# 8051_at89s52.net
KiCad netlist of a schematic drawn in Altium Designer
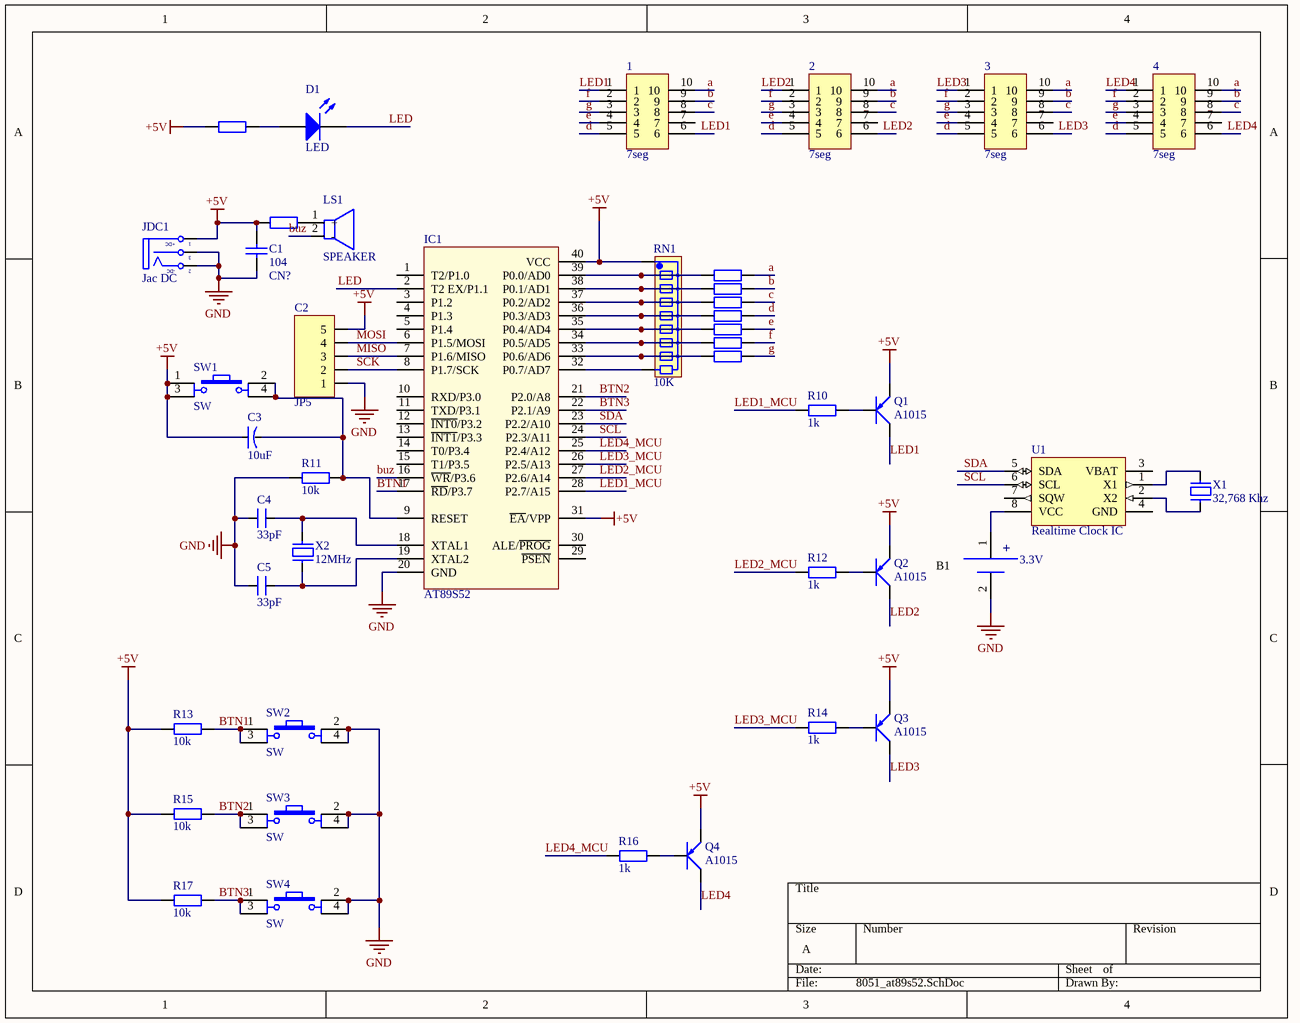
[diagram p0: 8051_at89s52.SchDoc]

(export (version "E")
  (design (tool "Eeschema 10.0.6"))
  (components
    (comp (ref "1")
      (value "7seg")
      (footprint "SM410361N")
      (description "7seg 0,36''")
      (libsource (lib "Schlib1") (part "SM410361N"))
    )
    (comp (ref "2")
      (value "7seg")
      (footprint "SM410361N")
      (description "7seg 0,36''")
      (libsource (lib "Schlib1") (part "SM410361N"))
    )
    (comp (ref "3")
      (value "7seg")
      (footprint "SM410361N")
      (description "7seg 0,36''")
      (libsource (lib "Schlib1") (part "SM410361N"))
    )
    (comp (ref "4")
      (value "7seg")
      (footprint "SM410361N")
      (description "7seg 0,36''")
      (libsource (lib "Schlib1") (part "SM410361N"))
    )
    (comp (ref "B1")
      (value "3.3V")
      (footprint "BATT-LI-Bott-22mm")
      (description "Battery holder")
      (fields
        (field (name "MANUFACTURER") "China")
        (field (name "Comment") "BATT-Holder")
        (field (name "PUBLISHER") "Hoang Nguyen")
      )
      (libsource (lib "hphonglib") (part "BATT-Holder"))
    )
    (comp (ref "C1")
      (value "104")
      (footprint "CAP_0805")
      (description "Capacitor (Semiconductor SIM Model)")
      (fields (field (name "ALTIUM_VALUE") "CN?") (field (name "PUBLISHER") "Altium Limited"))
      (libsource (lib "syhaunguyen") (part "Cap Semi"))
    )
    (comp (ref "C2")
      (value "JP5")
      (footprint "JP5-C1T")
      (description "WR-PHD 2.54 mm Angled Socket Header")
      (fields
        (field (name "MANUFACTURER") "Würth Elektronik eiSos GmbH")
        (field (name "PARTNO") "613005143121")
        (field (name "CREATED BY") "Karrer Zheng")
      )
      (libsource (lib "LIBRARY") (part "JP5"))
    )
    (comp (ref "C3")
      (value "10uF")
      (footprint "CA-ALU-2.54")
      (description "Capacitor (Semiconductor SIM Model)")
      (fields (field (name "PUBLISHER") "Altium Limited"))
      (libsource (lib "LIBRARY") (part "CN-ALU-DIP"))
    )
    (comp (ref "C4")
      (value "33pF")
      (footprint "CN1")
      (description "Cap np  1pF - 472pF")
      (libsource (lib "syhaunguyen") (part "CN1"))
    )
    (comp (ref "C5")
      (value "33pF")
      (footprint "CN1")
      (description "Cap np  1pF - 472pF")
      (libsource (lib "syhaunguyen") (part "CN1"))
    )
    (comp (ref "D1")
      (value "LED")
      (footprint "LED-0 5mm YELLOW")
      (description "Typical LED")
      (fields (field (name "PUBLISHER") "Altium Limited"))
      (libsource (lib "hphonglib") (part "LED"))
    )
    (comp (ref "IC1")
      (value "AT89S52")
      (footprint "DIP40/W0.6")
      (description "AT89S52, 8k Byte Flash Memory , 40 Pin")
      (libsource (lib "Schlib1") (part "AT89S52"))
    )
    (comp (ref "JDC1")
      (value "Jac DC")
      (footprint "DC3")
      (description "Jac DC input")
      (libsource (lib "LIBRARY") (part "DCIN"))
    )
    (comp (ref "LS1")
      (value "SPEAKER")
      (footprint "speaker")
      (fields (field (name "PUBLISHER") "Hoang Nguyen"))
      (libsource (lib "hphonglib") (part "SPEAKER"))
    )
    (comp (ref "Q1")
      (value "A1015")
      (footprint "QTO-92")
      (description "PNP 600mW, ECB")
      (libsource (lib "hphonglib") (part "A1015_1"))
    )
    (comp (ref "Q2")
      (value "A1015")
      (footprint "QTO-92")
      (description "PNP 600mW, ECB")
      (libsource (lib "hphonglib") (part "A1015_1"))
    )
    (comp (ref "Q3")
      (value "A1015")
      (footprint "QTO-92")
      (description "PNP 600mW, ECB")
      (libsource (lib "hphonglib") (part "A1015_1"))
    )
    (comp (ref "Q4")
      (value "A1015")
      (footprint "QTO-92")
      (description "PNP 600mW, ECB")
      (libsource (lib "hphonglib") (part "A1015_1"))
    )
    (comp (ref "R1")
      (value "1k")
      (footprint "R1/4W")
      (description "Resistor 1/4W")
      (libsource (lib "hphonglib") (part "R1/4W"))
    )
    (comp (ref "R2")
      (value "1k")
      (footprint "R1/4W")
      (description "Resistor 1/4W")
      (libsource (lib "hphonglib") (part "R1/4W"))
    )
    (comp (ref "R3")
      (value "1k")
      (footprint "R1/4W")
      (description "Resistor 1/4W")
      (libsource (lib "hphonglib") (part "R1/4W"))
    )
    (comp (ref "R4")
      (value "1k")
      (footprint "R1/4W")
      (description "Resistor 1/4W")
      (libsource (lib "hphonglib") (part "R1/4W"))
    )
    (comp (ref "R5")
      (value "1k")
      (footprint "R1/4W")
      (description "Resistor 1/4W")
      (libsource (lib "hphonglib") (part "R1/4W"))
    )
    (comp (ref "R6")
      (value "1k")
      (footprint "R1/4W")
      (description "Resistor 1/4W")
      (libsource (lib "hphonglib") (part "R1/4W"))
    )
    (comp (ref "R7")
      (value "1k")
      (footprint "R1/4W")
      (description "Resistor 1/4W")
      (libsource (lib "hphonglib") (part "R1/4W"))
    )
    (comp (ref "R8")
      (value "1k")
      (footprint "R1/4W")
      (description "Resistor 1/4W")
      (libsource (lib "hphonglib") (part "R1/4W"))
    )
    (comp (ref "R9")
      (value "1k")
      (footprint "R1/4W")
      (description "Resistor 1/4W")
      (libsource (lib "hphonglib") (part "R1/4W"))
    )
    (comp (ref "R10")
      (value "1k")
      (footprint "R1/4W")
      (description "Resistor 1/4W")
      (libsource (lib "hphonglib") (part "R1/4W"))
    )
    (comp (ref "R11")
      (value "10k")
      (footprint "RES-1/4W")
      (description "Resistor 1/4W")
      (libsource (lib "syhaunguyen") (part "R1/4W"))
    )
    (comp (ref "R12")
      (value "1k")
      (footprint "R1/4W")
      (description "Resistor 1/4W")
      (libsource (lib "hphonglib") (part "R1/4W"))
    )
    (comp (ref "R13")
      (value "10k")
      (footprint "R1/4W")
      (description "Resistor 1/4W")
      (libsource (lib "syhaunguyen") (part "R1/4W"))
    )
    (comp (ref "R14")
      (value "1k")
      (footprint "R1/4W")
      (description "Resistor 1/4W")
      (libsource (lib "hphonglib") (part "R1/4W"))
    )
    (comp (ref "R15")
      (value "10k")
      (footprint "R1/4W")
      (description "Resistor 1/4W")
      (libsource (lib "syhaunguyen") (part "R1/4W"))
    )
    (comp (ref "R16")
      (value "1k")
      (footprint "R1/4W")
      (description "Resistor 1/4W")
      (libsource (lib "hphonglib") (part "R1/4W"))
    )
    (comp (ref "R17")
      (value "10k")
      (footprint "R1/4W")
      (description "Resistor 1/4W")
      (libsource (lib "syhaunguyen") (part "R1/4W"))
    )
    (comp (ref "RN1")
      (value "10K")
      (footprint "RN8")
      (description "Resistor 8 (Thanh)")
      (libsource (lib "syhaunguyen") (part "RN8"))
    )
    (comp (ref "SW1")
      (value "SW")
      (footprint "SW4")
      (description "Switch button 4 pin")
      (libsource (lib "hphonglib") (part "SW4"))
    )
    (comp (ref "SW2")
      (value "SW")
      (footprint "SW4")
      (description "Switch button 4 pin")
      (libsource (lib "hphonglib") (part "SW4"))
    )
    (comp (ref "SW3")
      (value "SW")
      (footprint "SW4")
      (description "Switch button 4 pin")
      (libsource (lib "hphonglib") (part "SW4"))
    )
    (comp (ref "SW4")
      (value "SW")
      (footprint "SW4")
      (description "Switch button 4 pin")
      (libsource (lib "hphonglib") (part "SW4"))
    )
    (comp (ref "U1")
      (value "Realtime Clock IC")
      (footprint "DS1307.Dip8")
      (fields (field (name "MANUFACTURER") "Maxim"))
      (libsource (lib "hphonglib") (part "DS1307"))
    )
    (comp (ref "X1")
      (value "32,768 Khz")
      (footprint "XT32k")
      (description "Crystal 32,768kHz for timer real")
      (libsource (lib "hphonglib") (part "XT32k"))
    )
    (comp (ref "X2")
      (value "12MHz")
      (footprint "XT2")
      (description "Crystal For all Crystal 2pin.")
      (libsource (lib "syhaunguyen") (part "XT2"))
    )
  )
  (nets
    (net (code "1") (name "+5V") (class "Default")
      (node (ref "C1") (pin "2") (pinfunction "2_2") (pintype "passive"))
      (node (ref "C2") (pin "5") (pinfunction "5_5") (pintype "passive"))
      (node (ref "C3") (pin "1") (pinfunction "1_1") (pintype "passive"))
      (node (ref "IC1") (pin "31") (pinfunction "~{EA}/VPP_31") (pintype "passive"))
      (node (ref "IC1") (pin "40") (pinfunction "VCC_40") (pintype "passive"))
      (node (ref "JDC1") (pin "1") (pinfunction "T_1") (pintype "passive"))
      (node (ref "Q1") (pin "1") (pinfunction "E_1") (pintype "passive"))
      (node (ref "Q2") (pin "1") (pinfunction "E_1") (pintype "passive"))
      (node (ref "Q3") (pin "1") (pinfunction "E_1") (pintype "passive"))
      (node (ref "Q4") (pin "1") (pinfunction "E_1") (pintype "passive"))
      (node (ref "R1") (pin "1") (pinfunction "1_1") (pintype "passive"))
      (node (ref "R13") (pin "1") (pinfunction "1_1") (pintype "passive"))
      (node (ref "R15") (pin "1") (pinfunction "1_1") (pintype "passive"))
      (node (ref "R17") (pin "1") (pinfunction "1_1") (pintype "passive"))
      (node (ref "R2") (pin "1") (pinfunction "1_1") (pintype "passive"))
      (node (ref "RN1") (pin "1") (pinfunction "1_1") (pintype "passive"))
      (node (ref "SW1") (pin "1") (pintype "passive"))
      (node (ref "SW1") (pin "3") (pintype "passive"))
    )
    (net (code "2") (name "/BTN1") (class "Default")
      (node (ref "IC1") (pin "17") (pinfunction "~{RD}/P3.7_17") (pintype "passive"))
      (node (ref "R13") (pin "2") (pinfunction "2_2") (pintype "passive"))
      (node (ref "SW2") (pin "1") (pintype "passive"))
      (node (ref "SW2") (pin "3") (pintype "passive"))
    )
    (net (code "3") (name "/BTN2") (class "Default")
      (node (ref "IC1") (pin "21") (pinfunction "P2.0/A8_21") (pintype "passive"))
      (node (ref "R15") (pin "2") (pinfunction "2_2") (pintype "passive"))
      (node (ref "SW3") (pin "1") (pintype "passive"))
      (node (ref "SW3") (pin "3") (pintype "passive"))
    )
    (net (code "4") (name "/BTN3") (class "Default")
      (node (ref "IC1") (pin "22") (pinfunction "P2.1/A9_22") (pintype "passive"))
      (node (ref "R17") (pin "2") (pinfunction "2_2") (pintype "passive"))
      (node (ref "SW4") (pin "1") (pintype "passive"))
      (node (ref "SW4") (pin "3") (pintype "passive"))
    )
    (net (code "5") (name "/LED") (class "Default")
      (node (ref "D1") (pin "2") (pinfunction "K_2") (pintype "passive"))
      (node (ref "IC1") (pin "2") (pinfunction "T2_EX/P1.1_2") (pintype "passive"))
    )
    (net (code "6") (name "/LED1") (class "Default")
      (node (ref "1") (pin "1") (pinfunction "1_1") (pintype "passive"))
      (node (ref "1") (pin "6") (pinfunction "6_6") (pintype "passive"))
      (node (ref "Q1") (pin "2") (pinfunction "C_2") (pintype "passive"))
    )
    (net (code "7") (name "/LED1_MCU") (class "Default")
      (node (ref "IC1") (pin "28") (pinfunction "P2.7/A15_28") (pintype "passive"))
      (node (ref "R10") (pin "1") (pinfunction "1_1") (pintype "passive"))
    )
    (net (code "8") (name "/LED2") (class "Default")
      (node (ref "2") (pin "1") (pinfunction "1_1") (pintype "passive"))
      (node (ref "2") (pin "6") (pinfunction "6_6") (pintype "passive"))
      (node (ref "Q2") (pin "2") (pinfunction "C_2") (pintype "passive"))
    )
    (net (code "9") (name "/LED2_MCU") (class "Default")
      (node (ref "IC1") (pin "27") (pinfunction "P2.6/A14_27") (pintype "passive"))
      (node (ref "R12") (pin "1") (pinfunction "1_1") (pintype "passive"))
    )
    (net (code "10") (name "/LED3") (class "Default")
      (node (ref "3") (pin "1") (pinfunction "1_1") (pintype "passive"))
      (node (ref "3") (pin "6") (pinfunction "6_6") (pintype "passive"))
      (node (ref "Q3") (pin "2") (pinfunction "C_2") (pintype "passive"))
    )
    (net (code "11") (name "/LED3_MCU") (class "Default")
      (node (ref "IC1") (pin "26") (pinfunction "P2.5/A13_26") (pintype "passive"))
      (node (ref "R14") (pin "1") (pinfunction "1_1") (pintype "passive"))
    )
    (net (code "12") (name "/LED4") (class "Default")
      (node (ref "4") (pin "1") (pinfunction "1_1") (pintype "passive"))
      (node (ref "4") (pin "6") (pinfunction "6_6") (pintype "passive"))
      (node (ref "Q4") (pin "2") (pinfunction "C_2") (pintype "passive"))
    )
    (net (code "13") (name "/LED4_MCU") (class "Default")
      (node (ref "IC1") (pin "25") (pinfunction "P2.4/A12_25") (pintype "passive"))
      (node (ref "R16") (pin "1") (pinfunction "1_1") (pintype "passive"))
    )
    (net (code "14") (name "/MISO") (class "Default")
      (node (ref "C2") (pin "3") (pinfunction "3_3") (pintype "passive"))
      (node (ref "IC1") (pin "7") (pinfunction "P1.6/MISO_7") (pintype "passive"))
    )
    (net (code "15") (name "/MOSI") (class "Default")
      (node (ref "C2") (pin "4") (pinfunction "4_4") (pintype "passive"))
      (node (ref "IC1") (pin "6") (pinfunction "P1.5/MOSI_6") (pintype "passive"))
    )
    (net (code "16") (name "/SCK") (class "Default")
      (node (ref "C2") (pin "2") (pinfunction "2_2") (pintype "passive"))
      (node (ref "IC1") (pin "8") (pinfunction "P1.7/SCK_8") (pintype "passive"))
    )
    (net (code "17") (name "/SCL") (class "Default")
      (node (ref "IC1") (pin "24") (pinfunction "P2.3/A11_24") (pintype "passive"))
      (node (ref "U1") (pin "6") (pinfunction "SCL_6") (pintype "bidirectional"))
    )
    (net (code "18") (name "/SDA") (class "Default")
      (node (ref "IC1") (pin "23") (pinfunction "P2.2/A10_23") (pintype "passive"))
      (node (ref "U1") (pin "5") (pinfunction "SDA_5") (pintype "bidirectional"))
    )
    (net (code "19") (name "/a") (class "Default")
      (node (ref "1") (pin "10") (pinfunction "10_10") (pintype "passive"))
      (node (ref "2") (pin "10") (pinfunction "10_10") (pintype "passive"))
      (node (ref "3") (pin "10") (pinfunction "10_10") (pintype "passive"))
      (node (ref "4") (pin "10") (pinfunction "10_10") (pintype "passive"))
      (node (ref "R3") (pin "2") (pinfunction "2_2") (pintype "passive"))
    )
    (net (code "20") (name "/b") (class "Default")
      (node (ref "1") (pin "9") (pinfunction "9_9") (pintype "passive"))
      (node (ref "2") (pin "9") (pinfunction "9_9") (pintype "passive"))
      (node (ref "3") (pin "9") (pinfunction "9_9") (pintype "passive"))
      (node (ref "4") (pin "9") (pinfunction "9_9") (pintype "passive"))
      (node (ref "R4") (pin "2") (pinfunction "2_2") (pintype "passive"))
    )
    (net (code "21") (name "/buz") (class "Default")
      (node (ref "IC1") (pin "16") (pinfunction "~{WR}/P3.6_16") (pintype "passive"))
      (node (ref "LS1") (pin "2") (pinfunction "-_2") (pintype "passive"))
    )
    (net (code "22") (name "/c") (class "Default")
      (node (ref "1") (pin "8") (pinfunction "8_8") (pintype "passive"))
      (node (ref "2") (pin "8") (pinfunction "8_8") (pintype "passive"))
      (node (ref "3") (pin "8") (pinfunction "8_8") (pintype "passive"))
      (node (ref "4") (pin "8") (pinfunction "8_8") (pintype "passive"))
      (node (ref "R5") (pin "2") (pinfunction "2_2") (pintype "passive"))
    )
    (net (code "23") (name "/d") (class "Default")
      (node (ref "1") (pin "5") (pinfunction "5_5") (pintype "passive"))
      (node (ref "2") (pin "5") (pinfunction "5_5") (pintype "passive"))
      (node (ref "3") (pin "5") (pinfunction "5_5") (pintype "passive"))
      (node (ref "4") (pin "5") (pinfunction "5_5") (pintype "passive"))
      (node (ref "R6") (pin "2") (pinfunction "2_2") (pintype "passive"))
    )
    (net (code "24") (name "/e") (class "Default")
      (node (ref "1") (pin "4") (pinfunction "4_4") (pintype "passive"))
      (node (ref "2") (pin "4") (pinfunction "4_4") (pintype "passive"))
      (node (ref "3") (pin "4") (pinfunction "4_4") (pintype "passive"))
      (node (ref "4") (pin "4") (pinfunction "4_4") (pintype "passive"))
      (node (ref "R7") (pin "2") (pinfunction "2_2") (pintype "passive"))
    )
    (net (code "25") (name "/f") (class "Default")
      (node (ref "1") (pin "2") (pinfunction "2_2") (pintype "passive"))
      (node (ref "2") (pin "2") (pinfunction "2_2") (pintype "passive"))
      (node (ref "3") (pin "2") (pinfunction "2_2") (pintype "passive"))
      (node (ref "4") (pin "2") (pinfunction "2_2") (pintype "passive"))
      (node (ref "R8") (pin "2") (pinfunction "2_2") (pintype "passive"))
    )
    (net (code "26") (name "/g") (class "Default")
      (node (ref "1") (pin "3") (pinfunction "3_3") (pintype "passive"))
      (node (ref "2") (pin "3") (pinfunction "3_3") (pintype "passive"))
      (node (ref "3") (pin "3") (pinfunction "3_3") (pintype "passive"))
      (node (ref "4") (pin "3") (pinfunction "3_3") (pintype "passive"))
      (node (ref "R9") (pin "2") (pinfunction "2_2") (pintype "passive"))
    )
    (net (code "27") (name "GND") (class "Default")
      (node (ref "B1") (pin "2") (pinfunction "-_2") (pintype "passive"))
      (node (ref "C1") (pin "1") (pinfunction "1_1") (pintype "passive"))
      (node (ref "C2") (pin "1") (pinfunction "1_1") (pintype "passive"))
      (node (ref "C4") (pin "1") (pinfunction "1_1") (pintype "passive"))
      (node (ref "C5") (pin "1") (pinfunction "1_1") (pintype "passive"))
      (node (ref "IC1") (pin "20") (pinfunction "GND_20") (pintype "power_in"))
      (node (ref "JDC1") (pin "2") (pinfunction "TN_2") (pintype "passive"))
      (node (ref "JDC1") (pin "3") (pinfunction "S_3") (pintype "power_in"))
      (node (ref "R11") (pin "1") (pinfunction "1_1") (pintype "passive"))
      (node (ref "SW2") (pin "2") (pintype "passive"))
      (node (ref "SW2") (pin "4") (pintype "passive"))
      (node (ref "SW3") (pin "2") (pintype "passive"))
      (node (ref "SW3") (pin "4") (pintype "passive"))
      (node (ref "SW4") (pin "2") (pintype "passive"))
      (node (ref "SW4") (pin "4") (pintype "passive"))
    )
    (net (code "28") (name "Net-(B1-+)") (class "Default")
      (node (ref "B1") (pin "1") (pinfunction "+_1") (pintype "passive"))
      (node (ref "U1") (pin "8") (pinfunction "VCC_8") (pintype "power_in"))
    )
    (net (code "29") (name "Net-(D1-A)") (class "Default")
      (node (ref "D1") (pin "1") (pinfunction "A_1") (pintype "passive"))
      (node (ref "R1") (pin "2") (pinfunction "2_2") (pintype "passive"))
    )
    (net (code "30") (name "Net-(IC1-P0.0{slash}AD0)") (class "Default")
      (node (ref "IC1") (pin "39") (pinfunction "P0.0/AD0_39") (pintype "passive"))
      (node (ref "R3") (pin "1") (pinfunction "1_1") (pintype "passive"))
      (node (ref "RN1") (pin "2") (pinfunction "2_2") (pintype "passive"))
    )
    (net (code "31") (name "Net-(IC1-P0.1{slash}AD1)") (class "Default")
      (node (ref "IC1") (pin "38") (pinfunction "P0.1/AD1_38") (pintype "passive"))
      (node (ref "R4") (pin "1") (pinfunction "1_1") (pintype "passive"))
      (node (ref "RN1") (pin "3") (pinfunction "3_3") (pintype "passive"))
    )
    (net (code "32") (name "Net-(IC1-P0.2{slash}AD2)") (class "Default")
      (node (ref "IC1") (pin "37") (pinfunction "P0.2/AD2_37") (pintype "passive"))
      (node (ref "R5") (pin "1") (pinfunction "1_1") (pintype "passive"))
      (node (ref "RN1") (pin "4") (pinfunction "4_4") (pintype "passive"))
    )
    (net (code "33") (name "Net-(IC1-P0.3{slash}AD3)") (class "Default")
      (node (ref "IC1") (pin "36") (pinfunction "P0.3/AD3_36") (pintype "passive"))
      (node (ref "R6") (pin "1") (pinfunction "1_1") (pintype "passive"))
      (node (ref "RN1") (pin "5") (pinfunction "5_5") (pintype "passive"))
    )
    (net (code "34") (name "Net-(IC1-P0.4{slash}AD4)") (class "Default")
      (node (ref "IC1") (pin "35") (pinfunction "P0.4/AD4_35") (pintype "passive"))
      (node (ref "R7") (pin "1") (pinfunction "1_1") (pintype "passive"))
      (node (ref "RN1") (pin "6") (pinfunction "6_6") (pintype "passive"))
    )
    (net (code "35") (name "Net-(IC1-P0.5{slash}AD5)") (class "Default")
      (node (ref "IC1") (pin "34") (pinfunction "P0.5/AD5_34") (pintype "passive"))
      (node (ref "R8") (pin "1") (pinfunction "1_1") (pintype "passive"))
      (node (ref "RN1") (pin "7") (pinfunction "7_7") (pintype "passive"))
    )
    (net (code "36") (name "Net-(IC1-P0.6{slash}AD6)") (class "Default")
      (node (ref "IC1") (pin "33") (pinfunction "P0.6/AD6_33") (pintype "passive"))
      (node (ref "R9") (pin "1") (pinfunction "1_1") (pintype "passive"))
      (node (ref "RN1") (pin "8") (pinfunction "8_8") (pintype "passive"))
    )
    (net (code "37") (name "Net-(IC1-P0.7{slash}AD7)") (class "Default")
      (node (ref "IC1") (pin "32") (pinfunction "P0.7/AD7_32") (pintype "passive"))
      (node (ref "RN1") (pin "9") (pinfunction "9_9") (pintype "passive"))
    )
    (net (code "38") (name "Net-(IC1-RESET)") (class "Default")
      (node (ref "C3") (pin "2") (pinfunction "2_2") (pintype "passive"))
      (node (ref "IC1") (pin "9") (pinfunction "RESET_9") (pintype "passive"))
      (node (ref "R11") (pin "2") (pinfunction "2_2") (pintype "passive"))
      (node (ref "SW1") (pin "2") (pintype "passive"))
      (node (ref "SW1") (pin "4") (pintype "passive"))
    )
    (net (code "39") (name "Net-(IC1-XTAL1)") (class "Default")
      (node (ref "C4") (pin "2") (pinfunction "2_2") (pintype "passive"))
      (node (ref "IC1") (pin "18") (pinfunction "XTAL1_18") (pintype "passive"))
      (node (ref "X2") (pin "2") (pinfunction "2_2") (pintype "passive"))
    )
    (net (code "40") (name "Net-(IC1-XTAL2)") (class "Default")
      (node (ref "C5") (pin "2") (pinfunction "2_2") (pintype "passive"))
      (node (ref "IC1") (pin "19") (pinfunction "XTAL2_19") (pintype "passive"))
      (node (ref "X2") (pin "1") (pinfunction "1_1") (pintype "passive"))
    )
    (net (code "41") (name "Net-(LS1-+)") (class "Default")
      (node (ref "LS1") (pin "1") (pinfunction "+_1") (pintype "passive"))
      (node (ref "R2") (pin "2") (pinfunction "2_2") (pintype "passive"))
    )
    (net (code "42") (name "Net-(Q1-B)") (class "Default")
      (node (ref "Q1") (pin "3") (pinfunction "B_3") (pintype "passive"))
      (node (ref "R10") (pin "2") (pinfunction "2_2") (pintype "passive"))
    )
    (net (code "43") (name "Net-(Q2-B)") (class "Default")
      (node (ref "Q2") (pin "3") (pinfunction "B_3") (pintype "passive"))
      (node (ref "R12") (pin "2") (pinfunction "2_2") (pintype "passive"))
    )
    (net (code "44") (name "Net-(Q3-B)") (class "Default")
      (node (ref "Q3") (pin "3") (pinfunction "B_3") (pintype "passive"))
      (node (ref "R14") (pin "2") (pinfunction "2_2") (pintype "passive"))
    )
    (net (code "45") (name "Net-(Q4-B)") (class "Default")
      (node (ref "Q4") (pin "3") (pinfunction "B_3") (pintype "passive"))
      (node (ref "R16") (pin "2") (pinfunction "2_2") (pintype "passive"))
    )
    (net (code "46") (name "Net-(U1-X1)") (class "Default")
      (node (ref "U1") (pin "1") (pinfunction "X1_1") (pintype "output"))
      (node (ref "X1") (pin "2") (pinfunction "2_2") (pintype "passive"))
    )
    (net (code "47") (name "Net-(U1-X2)") (class "Default")
      (node (ref "U1") (pin "2") (pinfunction "X2_2") (pintype "input"))
      (node (ref "X1") (pin "1") (pinfunction "1_1") (pintype "passive"))
    )
    (net (code "48") (name "unconnected-(1-Pad7)") (class "Default")
      (node (ref "1") (pin "7") (pinfunction "7_7") (pintype "passive"))
    )
    (net (code "49") (name "unconnected-(2-Pad7)") (class "Default")
      (node (ref "2") (pin "7") (pinfunction "7_7") (pintype "passive"))
    )
    (net (code "50") (name "unconnected-(3-Pad7)") (class "Default")
      (node (ref "3") (pin "7") (pinfunction "7_7") (pintype "passive"))
    )
    (net (code "51") (name "unconnected-(4-Pad7)") (class "Default")
      (node (ref "4") (pin "7") (pinfunction "7_7") (pintype "passive"))
    )
    (net (code "52") (name "unconnected-(IC1-ALE{slash}~{PROG}-Pad30)") (class "Default")
      (node (ref "IC1") (pin "30") (pinfunction "ALE/~{PROG}_30") (pintype "passive"))
    )
    (net (code "53") (name "unconnected-(IC1-P1.2-Pad3)") (class "Default")
      (node (ref "IC1") (pin "3") (pinfunction "P1.2_3") (pintype "passive"))
    )
    (net (code "54") (name "unconnected-(IC1-P1.3-Pad4)") (class "Default")
      (node (ref "IC1") (pin "4") (pinfunction "P1.3_4") (pintype "passive"))
    )
    (net (code "55") (name "unconnected-(IC1-P1.4-Pad5)") (class "Default")
      (node (ref "IC1") (pin "5") (pinfunction "P1.4_5") (pintype "passive"))
    )
    (net (code "56") (name "unconnected-(IC1-RXD{slash}P3.0-Pad10)") (class "Default")
      (node (ref "IC1") (pin "10") (pinfunction "RXD/P3.0_10") (pintype "passive"))
    )
    (net (code "57") (name "unconnected-(IC1-T0{slash}P3.4-Pad14)") (class "Default")
      (node (ref "IC1") (pin "14") (pinfunction "T0/P3.4_14") (pintype "passive"))
    )
    (net (code "58") (name "unconnected-(IC1-T1{slash}P3.5-Pad15)") (class "Default")
      (node (ref "IC1") (pin "15") (pinfunction "T1/P3.5_15") (pintype "passive"))
    )
    (net (code "59") (name "unconnected-(IC1-T2{slash}P1.0-Pad1)") (class "Default")
      (node (ref "IC1") (pin "1") (pinfunction "T2/P1.0_1") (pintype "passive"))
    )
    (net (code "60") (name "unconnected-(IC1-TXD{slash}P3.1-Pad11)") (class "Default")
      (node (ref "IC1") (pin "11") (pinfunction "TXD/P3.1_11") (pintype "passive"))
    )
    (net (code "61") (name "unconnected-(IC1-~{INT0}{slash}P3.2-Pad12)") (class "Default")
      (node (ref "IC1") (pin "12") (pinfunction "~{INT0}/P3.2_12") (pintype "passive"))
    )
    (net (code "62") (name "unconnected-(IC1-~{INT1}{slash}P3.3-Pad13)") (class "Default")
      (node (ref "IC1") (pin "13") (pinfunction "~{INT1}/P3.3_13") (pintype "passive"))
    )
    (net (code "63") (name "unconnected-(IC1-~{PSEN}-Pad29)") (class "Default")
      (node (ref "IC1") (pin "29") (pinfunction "~{PSEN}_29") (pintype "passive"))
    )
    (net (code "64") (name "unconnected-(U1-GND-Pad4)") (class "Default")
      (node (ref "U1") (pin "4") (pinfunction "GND_4") (pintype "power_in"))
    )
    (net (code "65") (name "unconnected-(U1-SQW-Pad7)") (class "Default")
      (node (ref "U1") (pin "7") (pinfunction "SQW_7") (pintype "output"))
    )
    (net (code "66") (name "unconnected-(U1-VBAT-Pad3)") (class "Default")
      (node (ref "U1") (pin "3") (pinfunction "VBAT_3") (pintype "power_in"))
    )
  )
)
